# MotorBoard.net
KiCad netlist of a schematic drawn in EAGLE
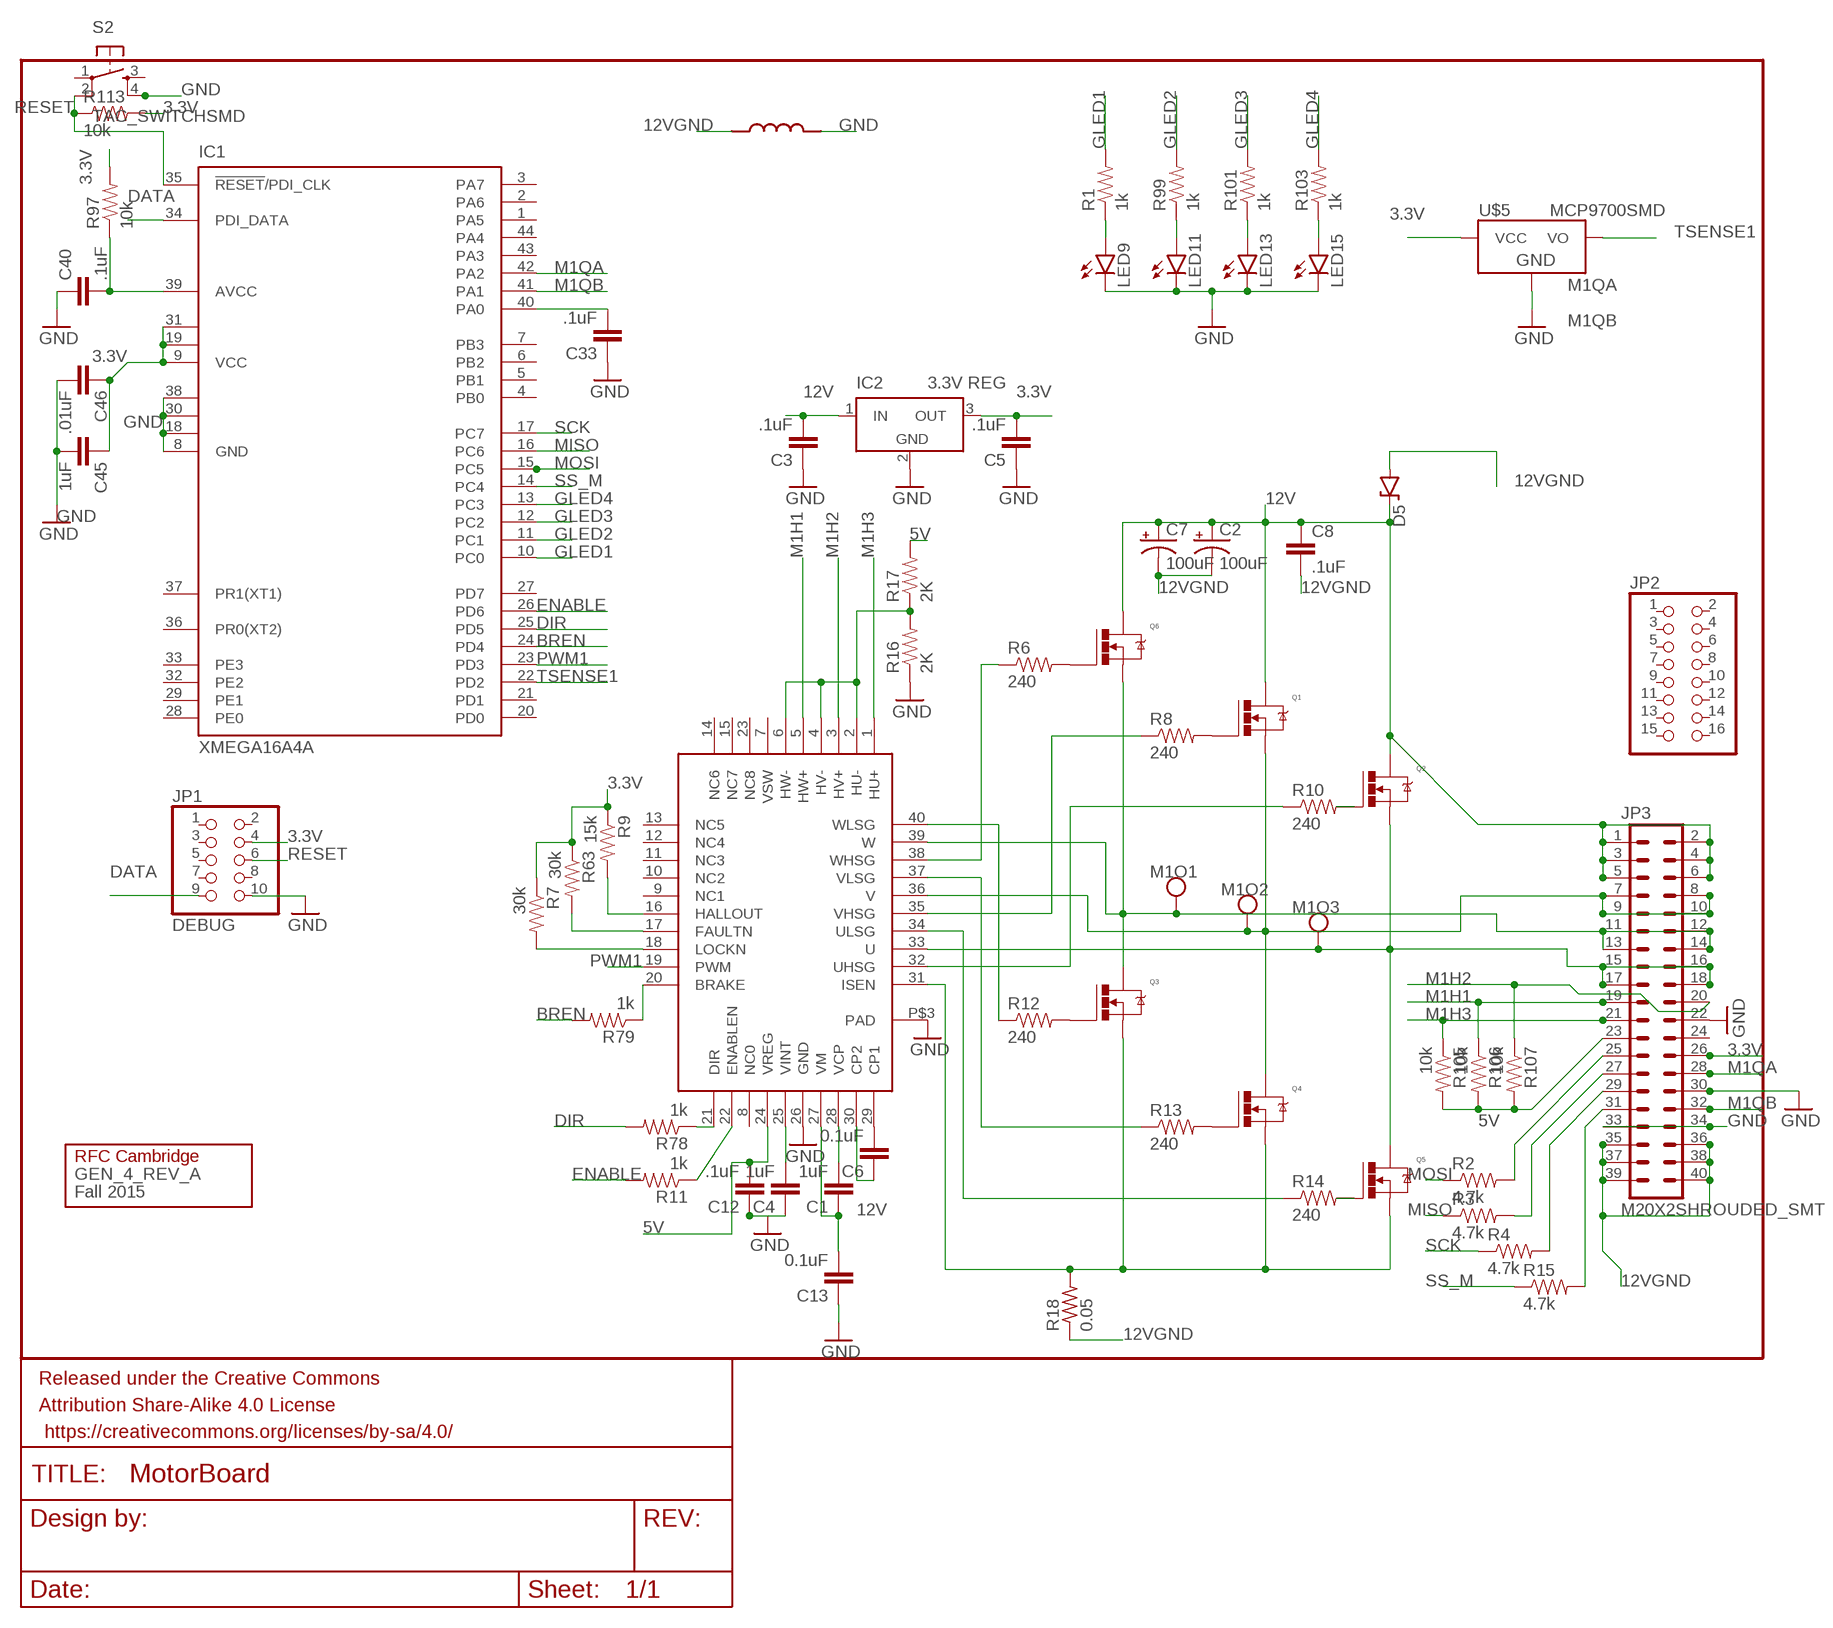
[diagram p0: schematic, sheet 1]

(export (version "E")
  (design (tool "Eeschema 10.0.6"))
  (components
    (comp (ref "C1")
      (value "1uF")
      (footprint "eagle-import:0805")
      (libsource (lib "eagle-import") (part "SparkFun-Passives_CAP0805"))
    )
    (comp (ref "C2")
      (value "100uF")
      (footprint "eagle-import:PANASONIC_D")
      (libsource (lib "eagle-import") (part "CAP-POLAR"))
    )
    (comp (ref "C3")
      (value ".1uF")
      (footprint "eagle-import:0805")
      (libsource (lib "eagle-import") (part "CAP0805"))
    )
    (comp (ref "C4")
      (value "1uF")
      (footprint "eagle-import:0805")
      (libsource (lib "eagle-import") (part "SparkFun-Passives_CAP0805"))
    )
    (comp (ref "C5")
      (value ".1uF")
      (footprint "eagle-import:0805")
      (libsource (lib "eagle-import") (part "CAP0805"))
    )
    (comp (ref "C6")
      (value "0.1uF")
      (footprint "eagle-import:0805")
      (libsource (lib "eagle-import") (part "SparkFun-Passives_CAP0805"))
    )
    (comp (ref "C7")
      (value "100uF")
      (footprint "eagle-import:PANASONIC_D")
      (libsource (lib "eagle-import") (part "CAP-POLAR"))
    )
    (comp (ref "C8")
      (value ".1uF")
      (footprint "eagle-import:0805")
      (libsource (lib "eagle-import") (part "SparkFun-Passives_CAP0805"))
    )
    (comp (ref "C12")
      (value ".1uF")
      (footprint "eagle-import:0805")
      (libsource (lib "eagle-import") (part "SparkFun-Passives_CAP0805"))
    )
    (comp (ref "C13")
      (value "0.1uF")
      (footprint "eagle-import:0805")
      (libsource (lib "eagle-import") (part "SparkFun-Passives_CAP0805"))
    )
    (comp (ref "C33")
      (value ".1uF")
      (footprint "eagle-import:0805")
      (libsource (lib "eagle-import") (part "CAP0805"))
    )
    (comp (ref "C40")
      (value ".1uF")
      (footprint "eagle-import:0805")
      (libsource (lib "eagle-import") (part "CAP0805"))
    )
    (comp (ref "C45")
      (value "1uF")
      (footprint "eagle-import:0805")
      (libsource (lib "eagle-import") (part "CAP0805"))
    )
    (comp (ref "C46")
      (value ".01uF")
      (footprint "eagle-import:0805")
      (libsource (lib "eagle-import") (part "CAP0805"))
    )
    (comp (ref "D5")
      (value "DIODE-ZENERDO214AC")
      (footprint "eagle-import:DO214AC")
      (libsource (lib "eagle-import") (part "DIODE-ZENERDO214AC"))
    )
    (comp (ref "FRAME7")
      (value "FRAME-LETTER")
      (footprint "eagle-import:CREATIVE_COMMONS")
      (libsource (lib "eagle-import") (part "FRAME-LETTER"))
    )
    (comp (ref "GEN_4_REV_A")
      (value "Fall 2015")
      (footprint "eagle-import:LOGO")
      (libsource (lib "eagle-import") (part "LOGO"))
    )
    (comp (ref "IC1")
      (value "XMEGA16A4A")
      (footprint "eagle-import:TQFP44")
      (libsource (lib "eagle-import") (part "XMEGA16A4A"))
    )
    (comp (ref "IC2")
      (value "3.3V REG")
      (footprint "eagle-import:SOT223")
      (fields (field (name "MPN") "LT1129CST-5#PBF"))
      (libsource (lib "eagle-import") (part "LT1129CST5"))
    )
    (comp (ref "JP1")
      (value "DEBUG")
      (footprint "eagle-import:2X05")
      (libsource (lib "eagle-import") (part "PINHD-2X5"))
    )
    (comp (ref "JP2")
      (value "PINHD-2X8")
      (footprint "eagle-import:2X08")
      (libsource (lib "eagle-import") (part "PINHD-2X8"))
    )
    (comp (ref "JP3")
      (value "M20X2SHROUDED_SMT")
      (footprint "eagle-import:2X20_SHROUDED_SMT")
      (libsource (lib "eagle-import") (part "M20X2SHROUDED_SMT"))
    )
    (comp (ref "LED9")
      (value "LED1206")
      (footprint "eagle-import:LED-1206")
      (libsource (lib "eagle-import") (part "LED1206"))
    )
    (comp (ref "LED11")
      (value "LED1206")
      (footprint "eagle-import:LED-1206")
      (libsource (lib "eagle-import") (part "LED1206"))
    )
    (comp (ref "LED13")
      (value "LED1206")
      (footprint "eagle-import:LED-1206")
      (libsource (lib "eagle-import") (part "LED1206"))
    )
    (comp (ref "LED15")
      (value "LED1206")
      (footprint "eagle-import:LED-1206")
      (libsource (lib "eagle-import") (part "LED1206"))
    )
    (comp (ref "M1O1")
      (value "TEST_PT")
      (footprint "eagle-import:TESTING_PT")
      (libsource (lib "eagle-import") (part "TEST_PT"))
    )
    (comp (ref "M1O2")
      (value "TEST_PT")
      (footprint "eagle-import:TESTING_PT")
      (libsource (lib "eagle-import") (part "TEST_PT"))
    )
    (comp (ref "M1O3")
      (value "TEST_PT")
      (footprint "eagle-import:TESTING_PT")
      (libsource (lib "eagle-import") (part "TEST_PT"))
    )
    (comp (ref "Q1")
      (value "N-MOSFET")
      (footprint "eagle-import:DPAK")
      (libsource (lib "eagle-import") (part "N-MOSFET"))
    )
    (comp (ref "Q2")
      (value "N-MOSFET")
      (footprint "eagle-import:DPAK")
      (libsource (lib "eagle-import") (part "N-MOSFET"))
    )
    (comp (ref "Q3")
      (value "N-MOSFET")
      (footprint "eagle-import:DPAK")
      (libsource (lib "eagle-import") (part "N-MOSFET"))
    )
    (comp (ref "Q4")
      (value "N-MOSFET")
      (footprint "eagle-import:DPAK")
      (libsource (lib "eagle-import") (part "N-MOSFET"))
    )
    (comp (ref "Q5")
      (value "N-MOSFET")
      (footprint "eagle-import:DPAK")
      (libsource (lib "eagle-import") (part "N-MOSFET"))
    )
    (comp (ref "Q6")
      (value "N-MOSFET")
      (footprint "eagle-import:DPAK")
      (libsource (lib "eagle-import") (part "N-MOSFET"))
    )
    (comp (ref "R1")
      (value "1k")
      (footprint "eagle-import:0805")
      (libsource (lib "eagle-import") (part "RESISTOR0805-RES"))
    )
    (comp (ref "R2")
      (value "4.7k")
      (footprint "eagle-import:0805")
      (libsource (lib "eagle-import") (part "RESISTOR0805-RES"))
    )
    (comp (ref "R3")
      (value "4.7k")
      (footprint "eagle-import:0805")
      (libsource (lib "eagle-import") (part "RESISTOR0805-RES"))
    )
    (comp (ref "R4")
      (value "4.7k")
      (footprint "eagle-import:0805")
      (libsource (lib "eagle-import") (part "RESISTOR0805-RES"))
    )
    (comp (ref "R6")
      (value "240")
      (footprint "eagle-import:0805")
      (libsource (lib "eagle-import") (part "SparkFun-Resistors_RESISTOR0805-RES"))
    )
    (comp (ref "R7")
      (value "30k")
      (footprint "eagle-import:0805")
      (libsource (lib "eagle-import") (part "SparkFun-Resistors_RESISTOR0805-RES"))
    )
    (comp (ref "R8")
      (value "240")
      (footprint "eagle-import:0805")
      (libsource (lib "eagle-import") (part "SparkFun-Resistors_RESISTOR0805-RES"))
    )
    (comp (ref "R9")
      (value "15k")
      (footprint "eagle-import:0805")
      (libsource (lib "eagle-import") (part "SparkFun-Resistors_RESISTOR0805-RES"))
    )
    (comp (ref "R10")
      (value "240")
      (footprint "eagle-import:0805")
      (libsource (lib "eagle-import") (part "SparkFun-Resistors_RESISTOR0805-RES"))
    )
    (comp (ref "R11")
      (value "1k")
      (footprint "eagle-import:0805")
      (libsource (lib "eagle-import") (part "SparkFun-Resistors_RESISTOR0805-RES"))
    )
    (comp (ref "R12")
      (value "240")
      (footprint "eagle-import:0805")
      (libsource (lib "eagle-import") (part "SparkFun-Resistors_RESISTOR0805-RES"))
    )
    (comp (ref "R13")
      (value "240")
      (footprint "eagle-import:0805")
      (libsource (lib "eagle-import") (part "SparkFun-Resistors_RESISTOR0805-RES"))
    )
    (comp (ref "R14")
      (value "240")
      (footprint "eagle-import:0805")
      (libsource (lib "eagle-import") (part "SparkFun-Resistors_RESISTOR0805-RES"))
    )
    (comp (ref "R15")
      (value "4.7k")
      (footprint "eagle-import:0805")
      (libsource (lib "eagle-import") (part "RESISTOR0805-RES"))
    )
    (comp (ref "R16")
      (value "2K")
      (footprint "eagle-import:0805")
      (libsource (lib "eagle-import") (part "SparkFun-Resistors_RESISTOR0805-RES"))
    )
    (comp (ref "R17")
      (value "2K")
      (footprint "eagle-import:0805")
      (libsource (lib "eagle-import") (part "SparkFun-Resistors_RESISTOR0805-RES"))
    )
    (comp (ref "R18")
      (value "0.05")
      (footprint "eagle-import:R2512")
      (libsource (lib "eagle-import") (part "R-US_R2512"))
    )
    (comp (ref "R63")
      (value "30k")
      (footprint "eagle-import:0805")
      (libsource (lib "eagle-import") (part "SparkFun-Resistors_RESISTOR0805-RES"))
    )
    (comp (ref "R78")
      (value "1k")
      (footprint "eagle-import:0805")
      (libsource (lib "eagle-import") (part "SparkFun-Resistors_RESISTOR0805-RES"))
    )
    (comp (ref "R79")
      (value "1k")
      (footprint "eagle-import:0805")
      (libsource (lib "eagle-import") (part "SparkFun-Resistors_RESISTOR0805-RES"))
    )
    (comp (ref "R97")
      (value "10k")
      (footprint "eagle-import:0805")
      (libsource (lib "eagle-import") (part "RESISTOR0805-RES"))
    )
    (comp (ref "R99")
      (value "1k")
      (footprint "eagle-import:0805")
      (libsource (lib "eagle-import") (part "RESISTOR0805-RES"))
    )
    (comp (ref "R101")
      (value "1k")
      (footprint "eagle-import:0805")
      (libsource (lib "eagle-import") (part "RESISTOR0805-RES"))
    )
    (comp (ref "R103")
      (value "1k")
      (footprint "eagle-import:0805")
      (libsource (lib "eagle-import") (part "RESISTOR0805-RES"))
    )
    (comp (ref "R105")
      (value "10k")
      (footprint "eagle-import:0805")
      (libsource (lib "eagle-import") (part "SparkFun-Resistors_RESISTOR0805-RES"))
    )
    (comp (ref "R106")
      (value "10k")
      (footprint "eagle-import:0805")
      (libsource (lib "eagle-import") (part "SparkFun-Resistors_RESISTOR0805-RES"))
    )
    (comp (ref "R107")
      (value "10k")
      (footprint "eagle-import:0805")
      (libsource (lib "eagle-import") (part "SparkFun-Resistors_RESISTOR0805-RES"))
    )
    (comp (ref "R113")
      (value "10k")
      (footprint "eagle-import:0805")
      (libsource (lib "eagle-import") (part "RESISTOR0805-RES"))
    )
    (comp (ref "S2")
      (value "TAC_SWITCHSMD")
      (footprint "eagle-import:TACTILE-SWITCH-SMD")
      (libsource (lib "eagle-import") (part "TAC_SWITCHSMD"))
    )
    (comp (ref "U$1")
      (value "DRV8307")
      (footprint "eagle-import:QFN40-6X6")
      (libsource (lib "eagle-import") (part "DRV8307"))
    )
    (comp (ref "U$2")
      (value "INDUCTOR")
      (footprint "eagle-import:0805")
      (libsource (lib "eagle-import") (part "INDUCTOR"))
    )
    (comp (ref "U$5")
      (value "MCP9700SMD")
      (footprint "eagle-import:SOT23-3")
      (libsource (lib "eagle-import") (part "MCP9700SMD"))
    )
  )
  (nets
    (net (code "1") (name "/3.3V") (class "Default")
      (node (ref "C45") (pin "1") (pinfunction "1_1") (pintype "passive"))
      (node (ref "C46") (pin "1") (pinfunction "1_1") (pintype "passive"))
      (node (ref "C5") (pin "2") (pinfunction "2_2") (pintype "passive"))
      (node (ref "IC1") (pin "19") (pinfunction "VCC1_19") (pintype "power_in"))
      (node (ref "IC1") (pin "31") (pinfunction "VCC2_31") (pintype "power_in"))
      (node (ref "IC1") (pin "9") (pinfunction "VCC_9") (pintype "power_in"))
      (node (ref "IC2") (pin "3") (pinfunction "OUT_3") (pintype "output"))
      (node (ref "JP1") (pin "4") (pinfunction "4_4") (pintype "passive"))
      (node (ref "JP3") (pin "26") (pinfunction "26_26") (pintype "passive"))
      (node (ref "R113") (pin "2") (pinfunction "2_2") (pintype "passive"))
      (node (ref "R63") (pin "1") (pinfunction "1_1") (pintype "passive"))
      (node (ref "R7") (pin "1") (pinfunction "1_1") (pintype "passive"))
      (node (ref "R9") (pin "1") (pinfunction "1_1") (pintype "passive"))
      (node (ref "R97") (pin "2") (pinfunction "2_2") (pintype "passive"))
      (node (ref "U$5") (pin "1") (pinfunction "VCC_1") (pintype "bidirectional"))
    )
    (net (code "2") (name "/5V") (class "Default")
      (node (ref "C12") (pin "2") (pinfunction "2_2") (pintype "passive"))
      (node (ref "JP3") (pin "23") (pinfunction "23_23") (pintype "passive"))
      (node (ref "R105") (pin "2") (pinfunction "2_2") (pintype "passive"))
      (node (ref "R106") (pin "2") (pinfunction "2_2") (pintype "passive"))
      (node (ref "R107") (pin "2") (pinfunction "2_2") (pintype "passive"))
      (node (ref "R17") (pin "2") (pinfunction "2_2") (pintype "passive"))
      (node (ref "U$1") (pin "24") (pinfunction "VREG_24") (pintype "bidirectional"))
    )
    (net (code "3") (name "/12V") (class "Default")
      (node (ref "C1") (pin "1") (pinfunction "1_1") (pintype "passive"))
      (node (ref "C13") (pin "2") (pinfunction "2_2") (pintype "passive"))
      (node (ref "C2") (pin "+") (pinfunction "+_+") (pintype "passive"))
      (node (ref "C3") (pin "2") (pinfunction "2_2") (pintype "passive"))
      (node (ref "C7") (pin "+") (pinfunction "+_+") (pintype "passive"))
      (node (ref "C8") (pin "1") (pinfunction "1_1") (pintype "passive"))
      (node (ref "D5") (pin "C") (pinfunction "C_C") (pintype "passive"))
      (node (ref "IC2") (pin "1") (pinfunction "IN_1") (pintype "input"))
      (node (ref "JP3") (pin "1") (pinfunction "1_1") (pintype "passive"))
      (node (ref "JP3") (pin "2") (pinfunction "2_2") (pintype "passive"))
      (node (ref "JP3") (pin "3") (pinfunction "3_3") (pintype "passive"))
      (node (ref "JP3") (pin "4") (pinfunction "4_4") (pintype "passive"))
      (node (ref "JP3") (pin "5") (pinfunction "5_5") (pintype "passive"))
      (node (ref "JP3") (pin "6") (pinfunction "6_6") (pintype "passive"))
      (node (ref "Q1") (pin "DRAIN") (pinfunction "P$1_DRAIN") (pintype "bidirectional"))
      (node (ref "Q2") (pin "DRAIN") (pinfunction "P$1_DRAIN") (pintype "bidirectional"))
      (node (ref "Q6") (pin "DRAIN") (pinfunction "P$1_DRAIN") (pintype "bidirectional"))
      (node (ref "U$1") (pin "27") (pinfunction "VM_27") (pintype "bidirectional"))
    )
    (net (code "4") (name "/12VGND") (class "Default")
      (node (ref "C2") (pin "-") (pinfunction "-_-") (pintype "passive"))
      (node (ref "C7") (pin "-") (pinfunction "-_-") (pintype "passive"))
      (node (ref "C8") (pin "2") (pinfunction "2_2") (pintype "passive"))
      (node (ref "D5") (pin "A") (pinfunction "A_A") (pintype "passive"))
      (node (ref "JP3") (pin "35") (pinfunction "35_35") (pintype "passive"))
      (node (ref "JP3") (pin "36") (pinfunction "36_36") (pintype "passive"))
      (node (ref "JP3") (pin "37") (pinfunction "37_37") (pintype "passive"))
      (node (ref "JP3") (pin "38") (pinfunction "38_38") (pintype "passive"))
      (node (ref "JP3") (pin "39") (pinfunction "39_39") (pintype "passive"))
      (node (ref "JP3") (pin "40") (pinfunction "40_40") (pintype "passive"))
      (node (ref "R18") (pin "1") (pinfunction "1_1") (pintype "passive"))
      (node (ref "U$2") (pin "1") (pinfunction "P$1_1") (pintype "bidirectional"))
    )
    (net (code "5") (name "/BREN") (class "Default")
      (node (ref "IC1") (pin "24") (pinfunction "PD4_24") (pintype "bidirectional"))
      (node (ref "R79") (pin "2") (pinfunction "2_2") (pintype "passive"))
    )
    (net (code "6") (name "/DATA") (class "Default")
      (node (ref "IC1") (pin "34") (pinfunction "PDI_DATA_34") (pintype "bidirectional"))
      (node (ref "JP1") (pin "9") (pinfunction "9_9") (pintype "passive"))
    )
    (net (code "7") (name "/DIR") (class "Default")
      (node (ref "IC1") (pin "25") (pinfunction "PD5_25") (pintype "bidirectional"))
      (node (ref "R78") (pin "2") (pinfunction "2_2") (pintype "passive"))
    )
    (net (code "8") (name "/ENABLE") (class "Default")
      (node (ref "IC1") (pin "26") (pinfunction "PD6_26") (pintype "bidirectional"))
      (node (ref "R11") (pin "2") (pinfunction "2_2") (pintype "passive"))
    )
    (net (code "9") (name "/GLED1") (class "Default")
      (node (ref "IC1") (pin "10") (pinfunction "PC0_10") (pintype "bidirectional"))
      (node (ref "R1") (pin "2") (pinfunction "2_2") (pintype "passive"))
    )
    (net (code "10") (name "/GLED2") (class "Default")
      (node (ref "IC1") (pin "11") (pinfunction "PC1_11") (pintype "bidirectional"))
      (node (ref "R99") (pin "2") (pinfunction "2_2") (pintype "passive"))
    )
    (net (code "11") (name "/GLED3") (class "Default")
      (node (ref "IC1") (pin "12") (pinfunction "PC2_12") (pintype "bidirectional"))
      (node (ref "R101") (pin "2") (pinfunction "2_2") (pintype "passive"))
    )
    (net (code "12") (name "/GLED4") (class "Default")
      (node (ref "IC1") (pin "13") (pinfunction "PC3_13") (pintype "bidirectional"))
      (node (ref "R103") (pin "2") (pinfunction "2_2") (pintype "passive"))
    )
    (net (code "13") (name "/M1H1") (class "Default")
      (node (ref "JP3") (pin "19") (pinfunction "19_19") (pintype "passive"))
      (node (ref "R106") (pin "1") (pinfunction "1_1") (pintype "passive"))
      (node (ref "U$1") (pin "5") (pinfunction "HW+_5") (pintype "bidirectional"))
    )
    (net (code "14") (name "/M1H2") (class "Default")
      (node (ref "JP3") (pin "20") (pinfunction "20_20") (pintype "passive"))
      (node (ref "R107") (pin "1") (pinfunction "1_1") (pintype "passive"))
      (node (ref "U$1") (pin "3") (pinfunction "HV+_3") (pintype "bidirectional"))
    )
    (net (code "15") (name "/M1H3") (class "Default")
      (node (ref "JP3") (pin "21") (pinfunction "21_21") (pintype "passive"))
      (node (ref "R105") (pin "1") (pinfunction "1_1") (pintype "passive"))
      (node (ref "U$1") (pin "1") (pinfunction "HU+_1") (pintype "bidirectional"))
    )
    (net (code "16") (name "/M1QA") (class "Default")
      (node (ref "IC1") (pin "42") (pinfunction "PA2_42") (pintype "bidirectional"))
      (node (ref "JP3") (pin "28") (pinfunction "28_28") (pintype "passive"))
    )
    (net (code "17") (name "/M1QB") (class "Default")
      (node (ref "IC1") (pin "41") (pinfunction "PA1_41") (pintype "bidirectional"))
      (node (ref "JP3") (pin "32") (pinfunction "32_32") (pintype "passive"))
    )
    (net (code "18") (name "/MISO") (class "Default")
      (node (ref "IC1") (pin "16") (pinfunction "PC6_16") (pintype "bidirectional"))
      (node (ref "R3") (pin "1") (pinfunction "1_1") (pintype "passive"))
    )
    (net (code "19") (name "/MOSI") (class "Default")
      (node (ref "IC1") (pin "15") (pinfunction "PC5_15") (pintype "bidirectional"))
      (node (ref "R2") (pin "1") (pinfunction "1_1") (pintype "passive"))
    )
    (net (code "20") (name "/PWM1") (class "Default")
      (node (ref "IC1") (pin "23") (pinfunction "PD3_23") (pintype "bidirectional"))
      (node (ref "U$1") (pin "19") (pinfunction "PWM_19") (pintype "bidirectional"))
    )
    (net (code "21") (name "/RESET") (class "Default")
      (node (ref "IC1") (pin "35") (pinfunction "~{RESET}/PDI_CLK_35") (pintype "bidirectional"))
      (node (ref "JP1") (pin "6") (pinfunction "6_6") (pintype "passive"))
      (node (ref "R113") (pin "1") (pinfunction "1_1") (pintype "passive"))
      (node (ref "S2") (pin "2") (pinfunction "2_2") (pintype "passive"))
    )
    (net (code "22") (name "/SCK") (class "Default")
      (node (ref "IC1") (pin "17") (pinfunction "PC7_17") (pintype "bidirectional"))
      (node (ref "R4") (pin "1") (pinfunction "1_1") (pintype "passive"))
    )
    (net (code "23") (name "/SS_M") (class "Default")
      (node (ref "IC1") (pin "14") (pinfunction "PC4_14") (pintype "bidirectional"))
      (node (ref "R15") (pin "1") (pinfunction "1_1") (pintype "passive"))
    )
    (net (code "24") (name "/TSENSE1") (class "Default")
      (node (ref "IC1") (pin "22") (pinfunction "PD2_22") (pintype "bidirectional"))
      (node (ref "U$5") (pin "2") (pinfunction "VO_2") (pintype "bidirectional"))
    )
    (net (code "25") (name "GND") (class "Default")
      (node (ref "C12") (pin "1") (pinfunction "1_1") (pintype "passive"))
      (node (ref "C13") (pin "1") (pinfunction "1_1") (pintype "passive"))
      (node (ref "C3") (pin "1") (pinfunction "1_1") (pintype "passive"))
      (node (ref "C33") (pin "1") (pinfunction "1_1") (pintype "passive"))
      (node (ref "C4") (pin "1") (pinfunction "1_1") (pintype "passive"))
      (node (ref "C40") (pin "1") (pinfunction "1_1") (pintype "passive"))
      (node (ref "C45") (pin "2") (pinfunction "2_2") (pintype "passive"))
      (node (ref "C46") (pin "2") (pinfunction "2_2") (pintype "passive"))
      (node (ref "C5") (pin "1") (pinfunction "1_1") (pintype "passive"))
      (node (ref "IC1") (pin "18") (pinfunction "GND1_18") (pintype "power_in"))
      (node (ref "IC1") (pin "30") (pinfunction "GND2_30") (pintype "power_in"))
      (node (ref "IC1") (pin "38") (pinfunction "GND3_38") (pintype "power_in"))
      (node (ref "IC1") (pin "8") (pinfunction "GND_8") (pintype "power_in"))
      (node (ref "IC2") (pin "2") (pinfunction "GND_2") (pintype "power_in"))
      (node (ref "JP1") (pin "10") (pinfunction "10_10") (pintype "passive"))
      (node (ref "JP3") (pin "22") (pinfunction "22_22") (pintype "passive"))
      (node (ref "JP3") (pin "30") (pinfunction "30_30") (pintype "passive"))
      (node (ref "JP3") (pin "33") (pinfunction "33_33") (pintype "passive"))
      (node (ref "JP3") (pin "34") (pinfunction "34_34") (pintype "passive"))
      (node (ref "LED11") (pin "C") (pinfunction "C_C") (pintype "passive"))
      (node (ref "LED13") (pin "C") (pinfunction "C_C") (pintype "passive"))
      (node (ref "LED15") (pin "C") (pinfunction "C_C") (pintype "passive"))
      (node (ref "LED9") (pin "C") (pinfunction "C_C") (pintype "passive"))
      (node (ref "R16") (pin "1") (pinfunction "1_1") (pintype "passive"))
      (node (ref "S2") (pin "4") (pinfunction "4_4") (pintype "passive"))
      (node (ref "U$1") (pin "26") (pinfunction "GND_26") (pintype "bidirectional"))
      (node (ref "U$1") (pin "P$3") (pinfunction "PAD_P$3") (pintype "bidirectional"))
      (node (ref "U$2") (pin "2") (pinfunction "P$2_2") (pintype "bidirectional"))
      (node (ref "U$5") (pin "3") (pinfunction "GND_3") (pintype "bidirectional"))
    )
    (net (code "26") (name "Net-(IC1-AVCC)") (class "Default")
      (node (ref "C40") (pin "2") (pinfunction "2_2") (pintype "passive"))
      (node (ref "IC1") (pin "39") (pinfunction "AVCC_39") (pintype "power_in"))
      (node (ref "R97") (pin "1") (pinfunction "1_1") (pintype "passive"))
    )
    (net (code "27") (name "Net-(IC1-PA0)") (class "Default")
      (node (ref "C33") (pin "2") (pinfunction "2_2") (pintype "passive"))
      (node (ref "IC1") (pin "40") (pinfunction "PA0_40") (pintype "bidirectional"))
    )
    (net (code "28") (name "Net-(JP3-Pad25)") (class "Default")
      (node (ref "JP3") (pin "25") (pinfunction "25_25") (pintype "passive"))
      (node (ref "R2") (pin "2") (pinfunction "2_2") (pintype "passive"))
    )
    (net (code "29") (name "Net-(JP3-Pad27)") (class "Default")
      (node (ref "JP3") (pin "27") (pinfunction "27_27") (pintype "passive"))
      (node (ref "R3") (pin "2") (pinfunction "2_2") (pintype "passive"))
    )
    (net (code "30") (name "Net-(JP3-Pad29)") (class "Default")
      (node (ref "JP3") (pin "29") (pinfunction "29_29") (pintype "passive"))
      (node (ref "R4") (pin "2") (pinfunction "2_2") (pintype "passive"))
    )
    (net (code "31") (name "Net-(JP3-Pad31)") (class "Default")
      (node (ref "JP3") (pin "31") (pinfunction "31_31") (pintype "passive"))
      (node (ref "R15") (pin "2") (pinfunction "2_2") (pintype "passive"))
    )
    (net (code "32") (name "Net-(LED9-PadA)") (class "Default")
      (node (ref "LED9") (pin "A") (pinfunction "A_A") (pintype "passive"))
      (node (ref "R1") (pin "1") (pinfunction "1_1") (pintype "passive"))
    )
    (net (code "33") (name "Net-(LED11-PadA)") (class "Default")
      (node (ref "LED11") (pin "A") (pinfunction "A_A") (pintype "passive"))
      (node (ref "R99") (pin "1") (pinfunction "1_1") (pintype "passive"))
    )
    (net (code "34") (name "Net-(LED13-PadA)") (class "Default")
      (node (ref "LED13") (pin "A") (pinfunction "A_A") (pintype "passive"))
      (node (ref "R101") (pin "1") (pinfunction "1_1") (pintype "passive"))
    )
    (net (code "35") (name "Net-(LED15-PadA)") (class "Default")
      (node (ref "LED15") (pin "A") (pinfunction "A_A") (pintype "passive"))
      (node (ref "R103") (pin "1") (pinfunction "1_1") (pintype "passive"))
    )
    (net (code "36") (name "Net-(Q1-P$2)") (class "Default")
      (node (ref "JP3") (pin "10") (pinfunction "10_10") (pintype "passive"))
      (node (ref "JP3") (pin "7") (pinfunction "7_7") (pintype "passive"))
      (node (ref "JP3") (pin "8") (pinfunction "8_8") (pintype "passive"))
      (node (ref "JP3") (pin "9") (pinfunction "9_9") (pintype "passive"))
      (node (ref "M1O2") (pin "P$1") (pinfunction "P$1_P$1") (pintype "bidirectional"))
      (node (ref "Q1") (pin "SOURCE") (pinfunction "P$2_SOURCE") (pintype "bidirectional"))
      (node (ref "Q4") (pin "DRAIN") (pinfunction "P$1_DRAIN") (pintype "bidirectional"))
      (node (ref "U$1") (pin "36") (pinfunction "V_36") (pintype "bidirectional"))
    )
    (net (code "37") (name "Net-(Q1-P$3)") (class "Default")
      (node (ref "Q1") (pin "GATE") (pinfunction "P$3_GATE") (pintype "bidirectional"))
      (node (ref "R8") (pin "2") (pinfunction "2_2") (pintype "passive"))
    )
    (net (code "38") (name "Net-(Q2-P$2)") (class "Default")
      (node (ref "JP3") (pin "15") (pinfunction "15_15") (pintype "passive"))
      (node (ref "JP3") (pin "16") (pinfunction "16_16") (pintype "passive"))
      (node (ref "JP3") (pin "17") (pinfunction "17_17") (pintype "passive"))
      (node (ref "JP3") (pin "18") (pinfunction "18_18") (pintype "passive"))
      (node (ref "M1O3") (pin "P$1") (pinfunction "P$1_P$1") (pintype "bidirectional"))
      (node (ref "Q2") (pin "SOURCE") (pinfunction "P$2_SOURCE") (pintype "bidirectional"))
      (node (ref "Q5") (pin "DRAIN") (pinfunction "P$1_DRAIN") (pintype "bidirectional"))
      (node (ref "U$1") (pin "33") (pinfunction "U_33") (pintype "bidirectional"))
    )
    (net (code "39") (name "Net-(Q2-P$3)") (class "Default")
      (node (ref "Q2") (pin "GATE") (pinfunction "P$3_GATE") (pintype "bidirectional"))
      (node (ref "R10") (pin "2") (pinfunction "2_2") (pintype "passive"))
    )
    (net (code "40") (name "Net-(Q3-P$1)") (class "Default")
      (node (ref "JP3") (pin "11") (pinfunction "11_11") (pintype "passive"))
      (node (ref "JP3") (pin "12") (pinfunction "12_12") (pintype "passive"))
      (node (ref "JP3") (pin "13") (pinfunction "13_13") (pintype "passive"))
      (node (ref "JP3") (pin "14") (pinfunction "14_14") (pintype "passive"))
      (node (ref "M1O1") (pin "P$1") (pinfunction "P$1_P$1") (pintype "bidirectional"))
      (node (ref "Q3") (pin "DRAIN") (pinfunction "P$1_DRAIN") (pintype "bidirectional"))
      (node (ref "Q6") (pin "SOURCE") (pinfunction "P$2_SOURCE") (pintype "bidirectional"))
      (node (ref "U$1") (pin "39") (pinfunction "W_39") (pintype "bidirectional"))
    )
    (net (code "41") (name "Net-(Q3-P$2)") (class "Default")
      (node (ref "Q3") (pin "SOURCE") (pinfunction "P$2_SOURCE") (pintype "bidirectional"))
      (node (ref "Q4") (pin "SOURCE") (pinfunction "P$2_SOURCE") (pintype "bidirectional"))
      (node (ref "Q5") (pin "SOURCE") (pinfunction "P$2_SOURCE") (pintype "bidirectional"))
      (node (ref "R18") (pin "2") (pinfunction "2_2") (pintype "passive"))
      (node (ref "U$1") (pin "31") (pinfunction "ISEN_31") (pintype "bidirectional"))
    )
    (net (code "42") (name "Net-(Q3-P$3)") (class "Default")
      (node (ref "Q3") (pin "GATE") (pinfunction "P$3_GATE") (pintype "bidirectional"))
      (node (ref "R12") (pin "2") (pinfunction "2_2") (pintype "passive"))
    )
    (net (code "43") (name "Net-(Q4-P$3)") (class "Default")
      (node (ref "Q4") (pin "GATE") (pinfunction "P$3_GATE") (pintype "bidirectional"))
      (node (ref "R13") (pin "2") (pinfunction "2_2") (pintype "passive"))
    )
    (net (code "44") (name "Net-(Q5-P$3)") (class "Default")
      (node (ref "Q5") (pin "GATE") (pinfunction "P$3_GATE") (pintype "bidirectional"))
      (node (ref "R14") (pin "2") (pinfunction "2_2") (pintype "passive"))
    )
    (net (code "45") (name "Net-(Q6-P$3)") (class "Default")
      (node (ref "Q6") (pin "GATE") (pinfunction "P$3_GATE") (pintype "bidirectional"))
      (node (ref "R6") (pin "2") (pinfunction "2_2") (pintype "passive"))
    )
    (net (code "46") (name "Net-(U$1-BRAKE)") (class "Default")
      (node (ref "R79") (pin "1") (pinfunction "1_1") (pintype "passive"))
      (node (ref "U$1") (pin "20") (pinfunction "BRAKE_20") (pintype "bidirectional"))
    )
    (net (code "47") (name "Net-(U$1-CP1)") (class "Default")
      (node (ref "C6") (pin "2") (pinfunction "2_2") (pintype "passive"))
      (node (ref "U$1") (pin "29") (pinfunction "CP1_29") (pintype "bidirectional"))
    )
    (net (code "48") (name "Net-(U$1-CP2)") (class "Default")
      (node (ref "C6") (pin "1") (pinfunction "1_1") (pintype "passive"))
      (node (ref "U$1") (pin "30") (pinfunction "CP2_30") (pintype "bidirectional"))
    )
    (net (code "49") (name "Net-(U$1-DIR)") (class "Default")
      (node (ref "R78") (pin "1") (pinfunction "1_1") (pintype "passive"))
      (node (ref "U$1") (pin "21") (pinfunction "DIR_21") (pintype "bidirectional"))
    )
    (net (code "50") (name "Net-(U$1-ENABLEN)") (class "Default")
      (node (ref "R11") (pin "1") (pinfunction "1_1") (pintype "passive"))
      (node (ref "U$1") (pin "22") (pinfunction "ENABLEN_22") (pintype "bidirectional"))
    )
    (net (code "51") (name "Net-(U$1-FAULTN)") (class "Default")
      (node (ref "R63") (pin "2") (pinfunction "2_2") (pintype "passive"))
      (node (ref "U$1") (pin "17") (pinfunction "FAULTN_17") (pintype "bidirectional"))
    )
    (net (code "52") (name "Net-(U$1-HALLOUT)") (class "Default")
      (node (ref "R9") (pin "2") (pinfunction "2_2") (pintype "passive"))
      (node (ref "U$1") (pin "16") (pinfunction "HALLOUT_16") (pintype "bidirectional"))
    )
    (net (code "53") (name "Net-(U$1-HU-)") (class "Default")
      (node (ref "R16") (pin "2") (pinfunction "2_2") (pintype "passive"))
      (node (ref "R17") (pin "1") (pinfunction "1_1") (pintype "passive"))
      (node (ref "U$1") (pin "2") (pinfunction "HU-_2") (pintype "bidirectional"))
      (node (ref "U$1") (pin "4") (pinfunction "HV-_4") (pintype "bidirectional"))
      (node (ref "U$1") (pin "6") (pinfunction "HW-_6") (pintype "bidirectional"))
    )
    (net (code "54") (name "Net-(U$1-LOCKN)") (class "Default")
      (node (ref "R7") (pin "2") (pinfunction "2_2") (pintype "passive"))
      (node (ref "U$1") (pin "18") (pinfunction "LOCKN_18") (pintype "bidirectional"))
    )
    (net (code "55") (name "Net-(U$1-UHSG)") (class "Default")
      (node (ref "R10") (pin "1") (pinfunction "1_1") (pintype "passive"))
      (node (ref "U$1") (pin "32") (pinfunction "UHSG_32") (pintype "bidirectional"))
    )
    (net (code "56") (name "Net-(U$1-ULSG)") (class "Default")
      (node (ref "R14") (pin "1") (pinfunction "1_1") (pintype "passive"))
      (node (ref "U$1") (pin "34") (pinfunction "ULSG_34") (pintype "bidirectional"))
    )
    (net (code "57") (name "Net-(U$1-VCP)") (class "Default")
      (node (ref "C1") (pin "2") (pinfunction "2_2") (pintype "passive"))
      (node (ref "U$1") (pin "28") (pinfunction "VCP_28") (pintype "bidirectional"))
    )
    (net (code "58") (name "Net-(U$1-VHSG)") (class "Default")
      (node (ref "R8") (pin "1") (pinfunction "1_1") (pintype "passive"))
      (node (ref "U$1") (pin "35") (pinfunction "VHSG_35") (pintype "bidirectional"))
    )
    (net (code "59") (name "Net-(U$1-VINT)") (class "Default")
      (node (ref "C4") (pin "2") (pinfunction "2_2") (pintype "passive"))
      (node (ref "U$1") (pin "25") (pinfunction "VINT_25") (pintype "bidirectional"))
    )
    (net (code "60") (name "Net-(U$1-VLSG)") (class "Default")
      (node (ref "R13") (pin "1") (pinfunction "1_1") (pintype "passive"))
      (node (ref "U$1") (pin "37") (pinfunction "VLSG_37") (pintype "bidirectional"))
    )
    (net (code "61") (name "Net-(U$1-WHSG)") (class "Default")
      (node (ref "R6") (pin "1") (pinfunction "1_1") (pintype "passive"))
      (node (ref "U$1") (pin "38") (pinfunction "WHSG_38") (pintype "bidirectional"))
    )
    (net (code "62") (name "Net-(U$1-WLSG)") (class "Default")
      (node (ref "R12") (pin "1") (pinfunction "1_1") (pintype "passive"))
      (node (ref "U$1") (pin "40") (pinfunction "WLSG_40") (pintype "bidirectional"))
    )
    (net (code "63") (name "unconnected-(IC1-PA3-Pad43)") (class "Default")
      (node (ref "IC1") (pin "43") (pinfunction "PA3_43") (pintype "bidirectional"))
    )
    (net (code "64") (name "unconnected-(IC1-PA4-Pad44)") (class "Default")
      (node (ref "IC1") (pin "44") (pinfunction "PA4_44") (pintype "bidirectional"))
    )
    (net (code "65") (name "unconnected-(IC1-PA5-Pad1)") (class "Default")
      (node (ref "IC1") (pin "1") (pinfunction "PA5_1") (pintype "bidirectional"))
    )
    (net (code "66") (name "unconnected-(IC1-PA6-Pad2)") (class "Default")
      (node (ref "IC1") (pin "2") (pinfunction "PA6_2") (pintype "bidirectional"))
    )
    (net (code "67") (name "unconnected-(IC1-PA7-Pad3)") (class "Default")
      (node (ref "IC1") (pin "3") (pinfunction "PA7_3") (pintype "bidirectional"))
    )
    (net (code "68") (name "unconnected-(IC1-PB0-Pad4)") (class "Default")
      (node (ref "IC1") (pin "4") (pinfunction "PB0_4") (pintype "bidirectional"))
    )
    (net (code "69") (name "unconnected-(IC1-PB1-Pad5)") (class "Default")
      (node (ref "IC1") (pin "5") (pinfunction "PB1_5") (pintype "bidirectional"))
    )
    (net (code "70") (name "unconnected-(IC1-PB2-Pad6)") (class "Default")
      (node (ref "IC1") (pin "6") (pinfunction "PB2_6") (pintype "bidirectional"))
    )
    (net (code "71") (name "unconnected-(IC1-PB3-Pad7)") (class "Default")
      (node (ref "IC1") (pin "7") (pinfunction "PB3_7") (pintype "bidirectional"))
    )
    (net (code "72") (name "unconnected-(IC1-PD0-Pad20)") (class "Default")
      (node (ref "IC1") (pin "20") (pinfunction "PD0_20") (pintype "bidirectional"))
    )
    (net (code "73") (name "unconnected-(IC1-PD1-Pad21)") (class "Default")
      (node (ref "IC1") (pin "21") (pinfunction "PD1_21") (pintype "bidirectional"))
    )
    (net (code "74") (name "unconnected-(IC1-PD7-Pad27)") (class "Default")
      (node (ref "IC1") (pin "27") (pinfunction "PD7_27") (pintype "bidirectional"))
    )
    (net (code "75") (name "unconnected-(IC1-PE0-Pad28)") (class "Default")
      (node (ref "IC1") (pin "28") (pinfunction "PE0_28") (pintype "bidirectional"))
    )
    (net (code "76") (name "unconnected-(IC1-PE1-Pad29)") (class "Default")
      (node (ref "IC1") (pin "29") (pinfunction "PE1_29") (pintype "bidirectional"))
    )
    (net (code "77") (name "unconnected-(IC1-PE2-Pad32)") (class "Default")
      (node (ref "IC1") (pin "32") (pinfunction "PE2_32") (pintype "bidirectional"))
    )
    (net (code "78") (name "unconnected-(IC1-PE3-Pad33)") (class "Default")
      (node (ref "IC1") (pin "33") (pinfunction "PE3_33") (pintype "bidirectional"))
    )
    (net (code "79") (name "unconnected-(IC1-PR0(XT2)-Pad36)") (class "Default")
      (node (ref "IC1") (pin "36") (pinfunction "PR0(XT2)_36") (pintype "bidirectional"))
    )
    (net (code "80") (name "unconnected-(IC1-PR1(XT1)-Pad37)") (class "Default")
      (node (ref "IC1") (pin "37") (pinfunction "PR1(XT1)_37") (pintype "bidirectional"))
    )
    (net (code "81") (name "unconnected-(JP1-Pad1)") (class "Default")
      (node (ref "JP1") (pin "1") (pinfunction "1_1") (pintype "passive"))
    )
    (net (code "82") (name "unconnected-(JP1-Pad2)") (class "Default")
      (node (ref "JP1") (pin "2") (pinfunction "2_2") (pintype "passive"))
    )
    (net (code "83") (name "unconnected-(JP1-Pad3)") (class "Default")
      (node (ref "JP1") (pin "3") (pinfunction "3_3") (pintype "passive"))
    )
    (net (code "84") (name "unconnected-(JP1-Pad5)") (class "Default")
      (node (ref "JP1") (pin "5") (pinfunction "5_5") (pintype "passive"))
    )
    (net (code "85") (name "unconnected-(JP1-Pad7)") (class "Default")
      (node (ref "JP1") (pin "7") (pinfunction "7_7") (pintype "passive"))
    )
    (net (code "86") (name "unconnected-(JP1-Pad8)") (class "Default")
      (node (ref "JP1") (pin "8") (pinfunction "8_8") (pintype "passive"))
    )
    (net (code "87") (name "unconnected-(JP2-Pad1)") (class "Default")
      (node (ref "JP2") (pin "1") (pinfunction "1_1") (pintype "passive"))
    )
    (net (code "88") (name "unconnected-(JP2-Pad2)") (class "Default")
      (node (ref "JP2") (pin "2") (pinfunction "2_2") (pintype "passive"))
    )
    (net (code "89") (name "unconnected-(JP2-Pad3)") (class "Default")
      (node (ref "JP2") (pin "3") (pinfunction "3_3") (pintype "passive"))
    )
    (net (code "90") (name "unconnected-(JP2-Pad4)") (class "Default")
      (node (ref "JP2") (pin "4") (pinfunction "4_4") (pintype "passive"))
    )
    (net (code "91") (name "unconnected-(JP2-Pad5)") (class "Default")
      (node (ref "JP2") (pin "5") (pinfunction "5_5") (pintype "passive"))
    )
    (net (code "92") (name "unconnected-(JP2-Pad6)") (class "Default")
      (node (ref "JP2") (pin "6") (pinfunction "6_6") (pintype "passive"))
    )
    (net (code "93") (name "unconnected-(JP2-Pad7)") (class "Default")
      (node (ref "JP2") (pin "7") (pinfunction "7_7") (pintype "passive"))
    )
    (net (code "94") (name "unconnected-(JP2-Pad8)") (class "Default")
      (node (ref "JP2") (pin "8") (pinfunction "8_8") (pintype "passive"))
    )
    (net (code "95") (name "unconnected-(JP2-Pad9)") (class "Default")
      (node (ref "JP2") (pin "9") (pinfunction "9_9") (pintype "passive"))
    )
    (net (code "96") (name "unconnected-(JP2-Pad10)") (class "Default")
      (node (ref "JP2") (pin "10") (pinfunction "10_10") (pintype "passive"))
    )
    (net (code "97") (name "unconnected-(JP2-Pad11)") (class "Default")
      (node (ref "JP2") (pin "11") (pinfunction "11_11") (pintype "passive"))
    )
    (net (code "98") (name "unconnected-(JP2-Pad12)") (class "Default")
      (node (ref "JP2") (pin "12") (pinfunction "12_12") (pintype "passive"))
    )
    (net (code "99") (name "unconnected-(JP2-Pad13)") (class "Default")
      (node (ref "JP2") (pin "13") (pinfunction "13_13") (pintype "passive"))
    )
    (net (code "100") (name "unconnected-(JP2-Pad14)") (class "Default")
      (node (ref "JP2") (pin "14") (pinfunction "14_14") (pintype "passive"))
    )
    (net (code "101") (name "unconnected-(JP2-Pad15)") (class "Default")
      (node (ref "JP2") (pin "15") (pinfunction "15_15") (pintype "passive"))
    )
    (net (code "102") (name "unconnected-(JP2-Pad16)") (class "Default")
      (node (ref "JP2") (pin "16") (pinfunction "16_16") (pintype "passive"))
    )
    (net (code "103") (name "unconnected-(JP3-Pad24)") (class "Default")
      (node (ref "JP3") (pin "24") (pinfunction "24_24") (pintype "passive"))
    )
    (net (code "104") (name "unconnected-(S2-Pad1)") (class "Default")
      (node (ref "S2") (pin "1") (pinfunction "1_1") (pintype "passive"))
    )
    (net (code "105") (name "unconnected-(S2-Pad3)") (class "Default")
      (node (ref "S2") (pin "3") (pinfunction "3_3") (pintype "passive"))
    )
    (net (code "106") (name "unconnected-(U$1-NC0-Pad8)") (class "Default")
      (node (ref "U$1") (pin "8") (pinfunction "NC0_8") (pintype "bidirectional"))
    )
    (net (code "107") (name "unconnected-(U$1-NC1-Pad9)") (class "Default")
      (node (ref "U$1") (pin "9") (pinfunction "NC1_9") (pintype "bidirectional"))
    )
    (net (code "108") (name "unconnected-(U$1-NC2-Pad10)") (class "Default")
      (node (ref "U$1") (pin "10") (pinfunction "NC2_10") (pintype "bidirectional"))
    )
    (net (code "109") (name "unconnected-(U$1-NC3-Pad11)") (class "Default")
      (node (ref "U$1") (pin "11") (pinfunction "NC3_11") (pintype "bidirectional"))
    )
    (net (code "110") (name "unconnected-(U$1-NC4-Pad12)") (class "Default")
      (node (ref "U$1") (pin "12") (pinfunction "NC4_12") (pintype "bidirectional"))
    )
    (net (code "111") (name "unconnected-(U$1-NC5-Pad13)") (class "Default")
      (node (ref "U$1") (pin "13") (pinfunction "NC5_13") (pintype "bidirectional"))
    )
    (net (code "112") (name "unconnected-(U$1-NC6-Pad14)") (class "Default")
      (node (ref "U$1") (pin "14") (pinfunction "NC6_14") (pintype "bidirectional"))
    )
    (net (code "113") (name "unconnected-(U$1-NC7-Pad15)") (class "Default")
      (node (ref "U$1") (pin "15") (pinfunction "NC7_15") (pintype "bidirectional"))
    )
    (net (code "114") (name "unconnected-(U$1-NC8-Pad23)") (class "Default")
      (node (ref "U$1") (pin "23") (pinfunction "NC8_23") (pintype "bidirectional"))
    )
    (net (code "115") (name "unconnected-(U$1-VSW-Pad7)") (class "Default")
      (node (ref "U$1") (pin "7") (pinfunction "VSW_7") (pintype "bidirectional"))
    )
  )
)
